# rev1.net
KiCad netlist of a schematic drawn in EAGLE
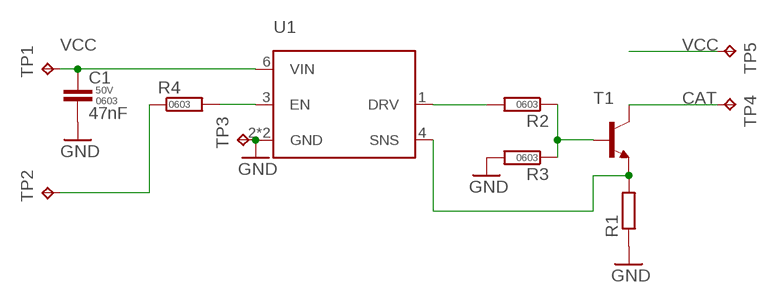
[diagram p0: schematic, sheet 1]

(export (version "E")
  (design (tool "Eeschema 10.0.6"))
  (components
    (comp (ref "C1")
      (value "47nF")
      (footprint "eagle-import:C0603")
      (fields (field (name "RATING") "10V") (field (name "PACKAGE") "0603") (field (name "RATING_1") "50V"))
      (libsource (lib "eagle-import") (part "CAP-0603"))
    )
    (comp (ref "R1")
      (value "R-EU_R1206")
      (footprint "eagle-import:R1206")
      (libsource (lib "eagle-import") (part "R-EU_R1206"))
    )
    (comp (ref "R2")
      (value "RES-0603")
      (footprint "eagle-import:R0603")
      (fields (field (name "PACKAGE") "0603"))
      (libsource (lib "eagle-import") (part "RES-0603"))
    )
    (comp (ref "R3")
      (value "RES-0603")
      (footprint "eagle-import:R0603")
      (fields (field (name "PACKAGE") "0603"))
      (libsource (lib "eagle-import") (part "RES-0603"))
    )
    (comp (ref "R4")
      (value "RES-0603")
      (footprint "eagle-import:R0603")
      (fields (field (name "PACKAGE") "0603"))
      (libsource (lib "eagle-import") (part "RES-0603"))
    )
    (comp (ref "T1")
      (value "BC868-NPN-SOT89-BCE")
      (footprint "eagle-import:SOT89-BCE")
      (libsource (lib "eagle-import") (part "-NPN-SOT89-BCEBC868"))
    )
    (comp (ref "TP1")
      (value "TPB2,54")
      (footprint "eagle-import:B2,54")
      (libsource (lib "eagle-import") (part "TPB2,54"))
    )
    (comp (ref "TP2")
      (value "TPB2,54")
      (footprint "eagle-import:B2,54")
      (libsource (lib "eagle-import") (part "TPB2,54"))
    )
    (comp (ref "TP3")
      (value "TPB2,54")
      (footprint "eagle-import:B2,54")
      (libsource (lib "eagle-import") (part "TPB2,54"))
    )
    (comp (ref "TP4")
      (value "TPB2,54")
      (footprint "eagle-import:B2,54")
      (libsource (lib "eagle-import") (part "TPB2,54"))
    )
    (comp (ref "TP5")
      (value "TPB2,54")
      (footprint "eagle-import:B2,54")
      (libsource (lib "eagle-import") (part "TPB2,54"))
    )
    (comp (ref "U1")
      (value "BCR450")
      (footprint "eagle-import:SC74_INFINEON")
      (libsource (lib "eagle-import") (part "BCR450"))
    )
  )
  (nets
    (net (code "1") (name "/CAT") (class "Default")
      (node (ref "T1") (pin "C") (pinfunction "C_C") (pintype "passive"))
      (node (ref "TP4") (pin "TP") (pinfunction "TP_TP") (pintype "input"))
    )
    (net (code "2") (name "/VCC") (class "Default")
      (node (ref "C1") (pin "1") (pinfunction "1_1") (pintype "passive"))
      (node (ref "TP1") (pin "TP") (pinfunction "TP_TP") (pintype "input"))
      (node (ref "TP5") (pin "TP") (pinfunction "TP_TP") (pintype "input"))
      (node (ref "U1") (pin "6") (pinfunction "VIN_6") (pintype "bidirectional"))
    )
    (net (code "3") (name "GND") (class "Default")
      (node (ref "C1") (pin "2") (pinfunction "2_2") (pintype "passive"))
      (node (ref "R1") (pin "1") (pinfunction "1_1") (pintype "passive"))
      (node (ref "R3") (pin "2") (pinfunction "2_2") (pintype "passive"))
      (node (ref "TP3") (pin "TP") (pinfunction "TP_TP") (pintype "input"))
      (node (ref "U1") (pin "2") (pinfunction "GND_2") (pintype "bidirectional"))
      (node (ref "U1") (pin "5") (pinfunction "GND_5") (pintype "bidirectional"))
    )
    (net (code "4") (name "Net-(R2-Pad1)") (class "Default")
      (node (ref "R2") (pin "1") (pinfunction "1_1") (pintype "passive"))
      (node (ref "R3") (pin "1") (pinfunction "1_1") (pintype "passive"))
      (node (ref "T1") (pin "B") (pinfunction "B_B") (pintype "passive"))
    )
    (net (code "5") (name "Net-(R4-Pad1)") (class "Default")
      (node (ref "R4") (pin "1") (pinfunction "1_1") (pintype "passive"))
      (node (ref "TP2") (pin "TP") (pinfunction "TP_TP") (pintype "input"))
    )
    (net (code "6") (name "Net-(U1-DRV)") (class "Default")
      (node (ref "R2") (pin "2") (pinfunction "2_2") (pintype "passive"))
      (node (ref "U1") (pin "1") (pinfunction "DRV_1") (pintype "bidirectional"))
    )
    (net (code "7") (name "Net-(U1-EN)") (class "Default")
      (node (ref "R4") (pin "2") (pinfunction "2_2") (pintype "passive"))
      (node (ref "U1") (pin "3") (pinfunction "EN_3") (pintype "bidirectional"))
    )
    (net (code "8") (name "Net-(U1-SNS)") (class "Default")
      (node (ref "R1") (pin "2") (pinfunction "2_2") (pintype "passive"))
      (node (ref "T1") (pin "E") (pinfunction "E_E") (pintype "passive"))
      (node (ref "U1") (pin "4") (pinfunction "SNS_4") (pintype "bidirectional"))
    )
  )
)
